# PCB.net
KiCad netlist of a schematic drawn in EAGLE
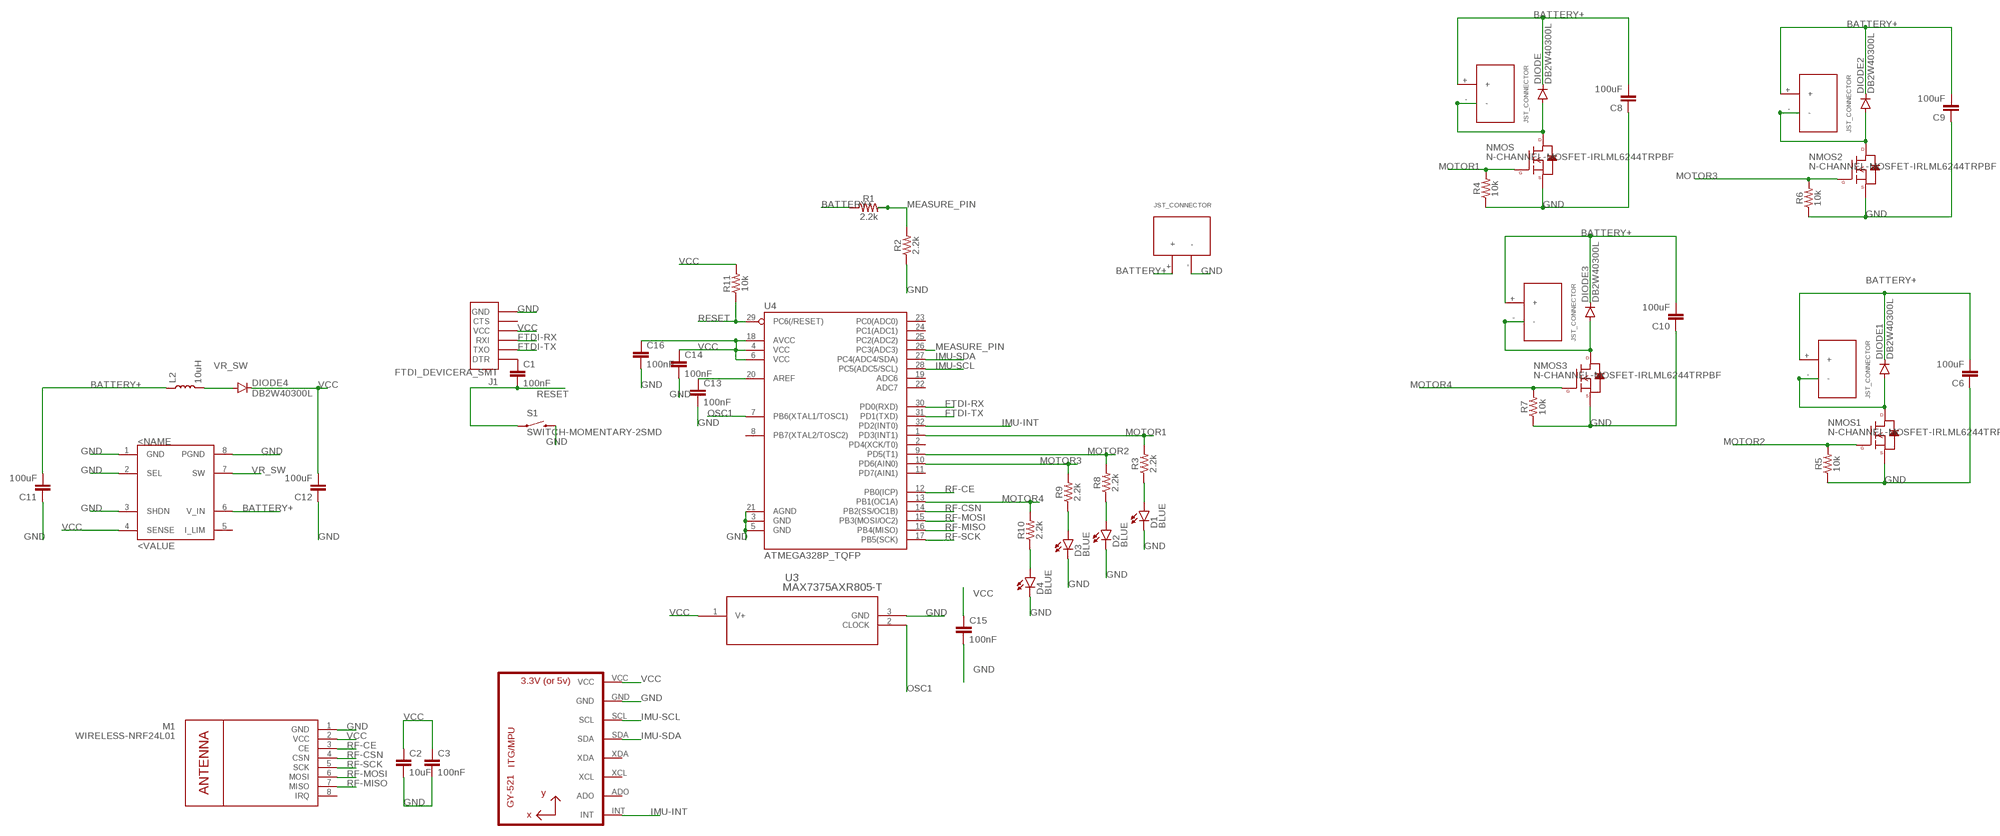
[diagram p0: schematic, sheet 1]

(export (version "E")
  (design (tool "Eeschema 10.0.6"))
  (components
    (comp (ref "BAT")
      (value "JST_CONNECTOR_FEMALE")
      (footprint "eagle-import:JST_CONNECTOR_FEMALE")
      (libsource (lib "eagle-import") (part "JST_CONNECTOR_FEMALE"))
    )
    (comp (ref "C1")
      (value "100nF")
      (footprint "eagle-import:0603-CAP")
      (libsource (lib "eagle-import") (part "0.1UF-25V(+80/-20%)(0603)"))
    )
    (comp (ref "C2")
      (value "10uF")
      (footprint "eagle-import:0603-CAP")
      (libsource (lib "eagle-import") (part "CAP0603-CAP"))
    )
    (comp (ref "C3")
      (value "100nF")
      (footprint "eagle-import:0603-CAP")
      (libsource (lib "eagle-import") (part "CAP0603-CAP"))
    )
    (comp (ref "C6")
      (value "100uF")
      (footprint "eagle-import:1206")
      (libsource (lib "eagle-import") (part "CAP1206"))
    )
    (comp (ref "C8")
      (value "100uF")
      (footprint "eagle-import:1206")
      (libsource (lib "eagle-import") (part "CAP1206"))
    )
    (comp (ref "C9")
      (value "100uF")
      (footprint "eagle-import:1206")
      (libsource (lib "eagle-import") (part "CAP1206"))
    )
    (comp (ref "C10")
      (value "100uF")
      (footprint "eagle-import:1206")
      (libsource (lib "eagle-import") (part "CAP1206"))
    )
    (comp (ref "C11")
      (value "100uF")
      (footprint "eagle-import:1206")
      (libsource (lib "eagle-import") (part "CAP1206"))
    )
    (comp (ref "C12")
      (value "100uF")
      (footprint "eagle-import:1206")
      (libsource (lib "eagle-import") (part "CAP1206"))
    )
    (comp (ref "C13")
      (value "100nF")
      (footprint "eagle-import:0603-CAP")
      (libsource (lib "eagle-import") (part "CAP0603-CAP"))
    )
    (comp (ref "C14")
      (value "100nF")
      (footprint "eagle-import:0603-CAP")
      (libsource (lib "eagle-import") (part "CAP0603-CAP"))
    )
    (comp (ref "C15")
      (value "100nF")
      (footprint "eagle-import:0603-CAP")
      (libsource (lib "eagle-import") (part "0.1UF-25V(+80/-20%)(0603)"))
    )
    (comp (ref "C16")
      (value "100nF")
      (footprint "eagle-import:0603-CAP")
      (libsource (lib "eagle-import") (part "CAP0603-CAP"))
    )
    (comp (ref "D1")
      (value "BLUE")
      (footprint "eagle-import:LED-0603")
      (fields (field (name "SPICEPREFIX") "D"))
      (libsource (lib "eagle-import") (part "LED-BLUE0603"))
    )
    (comp (ref "D2")
      (value "BLUE")
      (footprint "eagle-import:LED-0603")
      (libsource (lib "eagle-import") (part "LED-BLUE0603"))
    )
    (comp (ref "D3")
      (value "BLUE")
      (footprint "eagle-import:LED-0603")
      (libsource (lib "eagle-import") (part "LED-BLUE0603"))
    )
    (comp (ref "D4")
      (value "BLUE")
      (footprint "eagle-import:LED-0603")
      (libsource (lib "eagle-import") (part "LED-BLUE0603"))
    )
    (comp (ref "DIODE")
      (value "DB2W40300L")
      (footprint "eagle-import:MINI2-F3-B")
      (libsource (lib "eagle-import") (part "DB2W40300L"))
    )
    (comp (ref "DIODE1")
      (value "DB2W40300L")
      (footprint "eagle-import:MINI2-F3-B")
      (libsource (lib "eagle-import") (part "DB2W40300L"))
    )
    (comp (ref "DIODE2")
      (value "DB2W40300L")
      (footprint "eagle-import:MINI2-F3-B")
      (libsource (lib "eagle-import") (part "DB2W40300L"))
    )
    (comp (ref "DIODE3")
      (value "DB2W40300L")
      (footprint "eagle-import:MINI2-F3-B")
      (libsource (lib "eagle-import") (part "DB2W40300L"))
    )
    (comp (ref "DIODE4")
      (value "DB2W40300L")
      (footprint "eagle-import:MINI2-F3-B")
      (libsource (lib "eagle-import") (part "DB2W40300L"))
    )
    (comp (ref "J1")
      (value "FTDI_DEVICERA_SMT")
      (footprint "eagle-import:FTDI_DEVICE_RA_SMT")
      (libsource (lib "eagle-import") (part "FTDI_DEVICERA_SMT"))
    )
    (comp (ref "L2")
      (value "10uH")
      (footprint "eagle-import:0603")
      (libsource (lib "eagle-import") (part "INDUCTOR-0603-33NH"))
    )
    (comp (ref "M1")
      (value "WIRELESS-NRF24L01")
      (footprint "eagle-import:WIRELESS-NRF24L01")
      (libsource (lib "eagle-import") (part "WIRELESS-NRF24L01"))
    )
    (comp (ref "MOTOR")
      (value "JST_CONNECTOR_FEMALE")
      (footprint "eagle-import:JST_CONNECTOR_FEMALE")
      (libsource (lib "eagle-import") (part "JST_CONNECTOR_FEMALE"))
    )
    (comp (ref "MOTOR1")
      (value "JST_CONNECTOR_FEMALE")
      (footprint "eagle-import:JST_CONNECTOR_FEMALE")
      (libsource (lib "eagle-import") (part "JST_CONNECTOR_FEMALE"))
    )
    (comp (ref "MOTOR2")
      (value "JST_CONNECTOR_FEMALE")
      (footprint "eagle-import:JST_CONNECTOR_FEMALE")
      (libsource (lib "eagle-import") (part "JST_CONNECTOR_FEMALE"))
    )
    (comp (ref "MOTOR3")
      (value "JST_CONNECTOR_FEMALE")
      (footprint "eagle-import:JST_CONNECTOR_FEMALE")
      (libsource (lib "eagle-import") (part "JST_CONNECTOR_FEMALE"))
    )
    (comp (ref "NMOS")
      (value "N-CHANNEL-MOSFET-IRLML6244TRPBF")
      (footprint "eagle-import:SOT23-3")
      (libsource (lib "eagle-import") (part "N-CHANNEL-MOSFET-IRLML6244TRPBF"))
    )
    (comp (ref "NMOS1")
      (value "N-CHANNEL-MOSFET-IRLML6244TRPBF")
      (footprint "eagle-import:SOT23-3")
      (libsource (lib "eagle-import") (part "N-CHANNEL-MOSFET-IRLML6244TRPBF"))
    )
    (comp (ref "NMOS2")
      (value "N-CHANNEL-MOSFET-IRLML6244TRPBF")
      (footprint "eagle-import:SOT23-3")
      (libsource (lib "eagle-import") (part "N-CHANNEL-MOSFET-IRLML6244TRPBF"))
    )
    (comp (ref "NMOS3")
      (value "N-CHANNEL-MOSFET-IRLML6244TRPBF")
      (footprint "eagle-import:SOT23-3")
      (libsource (lib "eagle-import") (part "N-CHANNEL-MOSFET-IRLML6244TRPBF"))
    )
    (comp (ref "R1")
      (value "2.2k")
      (footprint "eagle-import:0603")
      (libsource (lib "eagle-import") (part "2.2KOHM-0603-1/10W-1%"))
    )
    (comp (ref "R2")
      (value "2.2k")
      (footprint "eagle-import:0603")
      (libsource (lib "eagle-import") (part "2.2KOHM-0603-1/10W-1%"))
    )
    (comp (ref "R3")
      (value "2.2k")
      (footprint "eagle-import:0603")
      (fields (field (name "SPICEPREFIX") "R"))
      (libsource (lib "eagle-import") (part "2.2KOHM-0603-1/10W-1%"))
    )
    (comp (ref "R4")
      (value "10k")
      (footprint "eagle-import:0603")
      (libsource (lib "eagle-import") (part "2.2KOHM-0603-1/10W-1%"))
    )
    (comp (ref "R5")
      (value "10k")
      (footprint "eagle-import:0603")
      (libsource (lib "eagle-import") (part "2.2KOHM-0603-1/10W-1%"))
    )
    (comp (ref "R6")
      (value "10k")
      (footprint "eagle-import:0603")
      (libsource (lib "eagle-import") (part "2.2KOHM-0603-1/10W-1%"))
    )
    (comp (ref "R7")
      (value "10k")
      (footprint "eagle-import:0603")
      (libsource (lib "eagle-import") (part "2.2KOHM-0603-1/10W-1%"))
    )
    (comp (ref "R8")
      (value "2.2k")
      (footprint "eagle-import:0603")
      (libsource (lib "eagle-import") (part "2.2KOHM-0603-1/10W-1%"))
    )
    (comp (ref "R9")
      (value "2.2k")
      (footprint "eagle-import:0603")
      (libsource (lib "eagle-import") (part "2.2KOHM-0603-1/10W-1%"))
    )
    (comp (ref "R10")
      (value "2.2k")
      (footprint "eagle-import:0603")
      (libsource (lib "eagle-import") (part "2.2KOHM-0603-1/10W-1%"))
    )
    (comp (ref "R11")
      (value "10k")
      (footprint "eagle-import:0603")
      (libsource (lib "eagle-import") (part "2.2KOHM-0603-1/10W-1%"))
    )
    (comp (ref "S1")
      (value "SWITCH-MOMENTARY-2SMD")
      (footprint "eagle-import:TACTILE-SWITCH-SMD")
      (libsource (lib "eagle-import") (part "SWITCH-MOMENTARY-2SMD"))
    )
    (comp (ref "U$4")
      (value "LT1300CS8#PBF-NDLT1300CS8#PBF-ND")
      (footprint "eagle-import:SOIC-8_S")
      (libsource (lib "eagle-import") (part "LT1300CS8#PBF-NDLT1300CS8#PBF-ND"))
    )
    (comp (ref "U2")
      (value "GY-521MPU6050")
      (footprint "eagle-import:GY-521")
      (libsource (lib "eagle-import") (part "GY-521MPU6050"))
    )
    (comp (ref "U3")
      (value "MAX7375AXR805-T")
      (footprint "eagle-import:21-0075D")
      (fields (field (name "MF") "Maxim Integrated") (field (name "MP") "MAX7375AXR805+T"))
      (libsource (lib "eagle-import") (part "MAX7375AXR805-T"))
    )
    (comp (ref "U4")
      (value "ATMEGA328P_TQFP")
      (footprint "eagle-import:TQFP32-08")
      (libsource (lib "eagle-import") (part "ATMEGA328P_TQFP"))
    )
  )
  (nets
    (net (code "1") (name "BATTERY+") (class "Default")
      (node (ref "BAT") (pin "+") (pinfunction "+_+") (pintype "bidirectional"))
      (node (ref "C10") (pin "2") (pinfunction "2_2") (pintype "passive"))
      (node (ref "C11") (pin "2") (pinfunction "2_2") (pintype "passive"))
      (node (ref "C6") (pin "2") (pinfunction "2_2") (pintype "passive"))
      (node (ref "C8") (pin "2") (pinfunction "2_2") (pintype "passive"))
      (node (ref "C9") (pin "2") (pinfunction "2_2") (pintype "passive"))
      (node (ref "DIODE") (pin "NEG") (pinfunction "GPIN_NEG") (pintype "passive"))
      (node (ref "DIODE1") (pin "NEG") (pinfunction "GPIN_NEG") (pintype "passive"))
      (node (ref "DIODE2") (pin "NEG") (pinfunction "GPIN_NEG") (pintype "passive"))
      (node (ref "DIODE3") (pin "NEG") (pinfunction "GPIN_NEG") (pintype "passive"))
      (node (ref "L2") (pin "1") (pinfunction "1_1") (pintype "passive"))
      (node (ref "MOTOR") (pin "+") (pinfunction "+_+") (pintype "bidirectional"))
      (node (ref "MOTOR1") (pin "+") (pinfunction "+_+") (pintype "bidirectional"))
      (node (ref "MOTOR2") (pin "+") (pinfunction "+_+") (pintype "bidirectional"))
      (node (ref "MOTOR3") (pin "+") (pinfunction "+_+") (pintype "bidirectional"))
      (node (ref "R1") (pin "1") (pinfunction "1_1") (pintype "passive"))
      (node (ref "U$4") (pin "6") (pinfunction "V_IN_6") (pintype "bidirectional"))
    )
    (net (code "2") (name "FTDI-RX") (class "Default")
      (node (ref "J1") (pin "3") (pinfunction "RXI_3") (pintype "bidirectional"))
      (node (ref "U4") (pin "30") (pinfunction "PD0(RXD)_30") (pintype "bidirectional"))
    )
    (net (code "3") (name "FTDI-TX") (class "Default")
      (node (ref "J1") (pin "2") (pinfunction "TXO_2") (pintype "bidirectional"))
      (node (ref "U4") (pin "31") (pinfunction "PD1(TXD)_31") (pintype "bidirectional"))
    )
    (net (code "4") (name "GND") (class "Default")
      (node (ref "BAT") (pin "-") (pinfunction "-_-") (pintype "bidirectional"))
      (node (ref "C10") (pin "1") (pinfunction "1_1") (pintype "passive"))
      (node (ref "C11") (pin "1") (pinfunction "1_1") (pintype "passive"))
      (node (ref "C12") (pin "1") (pinfunction "1_1") (pintype "passive"))
      (node (ref "C13") (pin "2") (pinfunction "2_2") (pintype "passive"))
      (node (ref "C14") (pin "2") (pinfunction "2_2") (pintype "passive"))
      (node (ref "C15") (pin "2") (pinfunction "2_2") (pintype "passive"))
      (node (ref "C16") (pin "2") (pinfunction "2_2") (pintype "passive"))
      (node (ref "C2") (pin "2") (pinfunction "2_2") (pintype "passive"))
      (node (ref "C3") (pin "2") (pinfunction "2_2") (pintype "passive"))
      (node (ref "C6") (pin "1") (pinfunction "1_1") (pintype "passive"))
      (node (ref "C8") (pin "1") (pinfunction "1_1") (pintype "passive"))
      (node (ref "C9") (pin "1") (pinfunction "1_1") (pintype "passive"))
      (node (ref "D1") (pin "C") (pinfunction "C_C") (pintype "passive"))
      (node (ref "D2") (pin "C") (pinfunction "C_C") (pintype "passive"))
      (node (ref "D3") (pin "C") (pinfunction "C_C") (pintype "passive"))
      (node (ref "D4") (pin "C") (pinfunction "C_C") (pintype "passive"))
      (node (ref "J1") (pin "6") (pinfunction "GND_6") (pintype "bidirectional"))
      (node (ref "M1") (pin "1") (pinfunction "GND_1") (pintype "power_in"))
      (node (ref "NMOS") (pin "2") (pinfunction "S_2") (pintype "passive"))
      (node (ref "NMOS1") (pin "2") (pinfunction "S_2") (pintype "passive"))
      (node (ref "NMOS2") (pin "2") (pinfunction "S_2") (pintype "passive"))
      (node (ref "NMOS3") (pin "2") (pinfunction "S_2") (pintype "passive"))
      (node (ref "R2") (pin "1") (pinfunction "1_1") (pintype "passive"))
      (node (ref "R4") (pin "1") (pinfunction "1_1") (pintype "passive"))
      (node (ref "R5") (pin "1") (pinfunction "1_1") (pintype "passive"))
      (node (ref "R6") (pin "1") (pinfunction "1_1") (pintype "passive"))
      (node (ref "R7") (pin "1") (pinfunction "1_1") (pintype "passive"))
      (node (ref "S1") (pin "3") (pinfunction "2_3") (pintype "passive"))
      (node (ref "U$4") (pin "1") (pinfunction "GND_1") (pintype "bidirectional"))
      (node (ref "U$4") (pin "2") (pinfunction "SEL_2") (pintype "bidirectional"))
      (node (ref "U$4") (pin "3") (pinfunction "SHDN_3") (pintype "bidirectional"))
      (node (ref "U$4") (pin "8") (pinfunction "PGND_8") (pintype "bidirectional"))
      (node (ref "U2") (pin "GND") (pinfunction "GND_GND") (pintype "bidirectional"))
      (node (ref "U3") (pin "3") (pinfunction "GND_3") (pintype "power_in"))
      (node (ref "U4") (pin "21") (pinfunction "AGND_21") (pintype "bidirectional"))
      (node (ref "U4") (pin "3") (pinfunction "GND_3") (pintype "bidirectional"))
      (node (ref "U4") (pin "5") (pinfunction "GND_5") (pintype "bidirectional"))
    )
    (net (code "5") (name "IMU-INT") (class "Default")
      (node (ref "U2") (pin "INT") (pinfunction "INT_INT") (pintype "bidirectional"))
      (node (ref "U4") (pin "32") (pinfunction "PD2(INT0)_32") (pintype "bidirectional"))
    )
    (net (code "6") (name "IMU-SCL") (class "Default")
      (node (ref "U2") (pin "SCL") (pinfunction "SCL_SCL") (pintype "bidirectional"))
      (node (ref "U4") (pin "28") (pinfunction "PC5(ADC5/SCL)_28") (pintype "bidirectional"))
    )
    (net (code "7") (name "IMU-SDA") (class "Default")
      (node (ref "U2") (pin "SDA") (pinfunction "SDA_SDA") (pintype "bidirectional"))
      (node (ref "U4") (pin "27") (pinfunction "PC4(ADC4/SDA)_27") (pintype "bidirectional"))
    )
    (net (code "8") (name "MEASURE_PIN") (class "Default")
      (node (ref "R1") (pin "2") (pinfunction "2_2") (pintype "passive"))
      (node (ref "R2") (pin "2") (pinfunction "2_2") (pintype "passive"))
      (node (ref "U4") (pin "26") (pinfunction "PC3(ADC3)_26") (pintype "bidirectional"))
    )
    (net (code "9") (name "MOTOR1") (class "Default")
      (node (ref "NMOS") (pin "1") (pinfunction "G_1") (pintype "passive"))
      (node (ref "R3") (pin "2") (pinfunction "2_2") (pintype "passive"))
      (node (ref "R4") (pin "2") (pinfunction "2_2") (pintype "passive"))
      (node (ref "U4") (pin "1") (pinfunction "PD3(INT1)_1") (pintype "bidirectional"))
    )
    (net (code "10") (name "MOTOR2") (class "Default")
      (node (ref "NMOS1") (pin "1") (pinfunction "G_1") (pintype "passive"))
      (node (ref "R5") (pin "2") (pinfunction "2_2") (pintype "passive"))
      (node (ref "R8") (pin "2") (pinfunction "2_2") (pintype "passive"))
      (node (ref "U4") (pin "9") (pinfunction "PD5(T1)_9") (pintype "bidirectional"))
    )
    (net (code "11") (name "MOTOR3") (class "Default")
      (node (ref "NMOS2") (pin "1") (pinfunction "G_1") (pintype "passive"))
      (node (ref "R6") (pin "2") (pinfunction "2_2") (pintype "passive"))
      (node (ref "R9") (pin "2") (pinfunction "2_2") (pintype "passive"))
      (node (ref "U4") (pin "10") (pinfunction "PD6(AIN0)_10") (pintype "bidirectional"))
    )
    (net (code "12") (name "MOTOR4") (class "Default")
      (node (ref "NMOS3") (pin "1") (pinfunction "G_1") (pintype "passive"))
      (node (ref "R10") (pin "2") (pinfunction "2_2") (pintype "passive"))
      (node (ref "R7") (pin "2") (pinfunction "2_2") (pintype "passive"))
      (node (ref "U4") (pin "13") (pinfunction "PB1(OC1A)_13") (pintype "bidirectional"))
    )
    (net (code "13") (name "Net-(D1-PadA)") (class "Default")
      (node (ref "D1") (pin "A") (pinfunction "A_A") (pintype "passive"))
      (node (ref "R3") (pin "1") (pinfunction "1_1") (pintype "passive"))
    )
    (net (code "14") (name "Net-(D2-PadA)") (class "Default")
      (node (ref "D2") (pin "A") (pinfunction "A_A") (pintype "passive"))
      (node (ref "R8") (pin "1") (pinfunction "1_1") (pintype "passive"))
    )
    (net (code "15") (name "Net-(D3-PadA)") (class "Default")
      (node (ref "D3") (pin "A") (pinfunction "A_A") (pintype "passive"))
      (node (ref "R9") (pin "1") (pinfunction "1_1") (pintype "passive"))
    )
    (net (code "16") (name "Net-(D4-PadA)") (class "Default")
      (node (ref "D4") (pin "A") (pinfunction "A_A") (pintype "passive"))
      (node (ref "R10") (pin "1") (pinfunction "1_1") (pintype "passive"))
    )
    (net (code "17") (name "Net-(DIODE-PPIN)") (class "Default")
      (node (ref "DIODE") (pin "POS") (pinfunction "PPIN_POS") (pintype "passive"))
      (node (ref "MOTOR") (pin "-") (pinfunction "-_-") (pintype "bidirectional"))
      (node (ref "NMOS") (pin "3") (pinfunction "D_3") (pintype "passive"))
    )
    (net (code "18") (name "Net-(DIODE1-PPIN)") (class "Default")
      (node (ref "DIODE1") (pin "POS") (pinfunction "PPIN_POS") (pintype "passive"))
      (node (ref "MOTOR1") (pin "-") (pinfunction "-_-") (pintype "bidirectional"))
      (node (ref "NMOS1") (pin "3") (pinfunction "D_3") (pintype "passive"))
    )
    (net (code "19") (name "Net-(DIODE2-PPIN)") (class "Default")
      (node (ref "DIODE2") (pin "POS") (pinfunction "PPIN_POS") (pintype "passive"))
      (node (ref "MOTOR2") (pin "-") (pinfunction "-_-") (pintype "bidirectional"))
      (node (ref "NMOS2") (pin "3") (pinfunction "D_3") (pintype "passive"))
    )
    (net (code "20") (name "Net-(DIODE3-PPIN)") (class "Default")
      (node (ref "DIODE3") (pin "POS") (pinfunction "PPIN_POS") (pintype "passive"))
      (node (ref "MOTOR3") (pin "-") (pinfunction "-_-") (pintype "bidirectional"))
      (node (ref "NMOS3") (pin "3") (pinfunction "D_3") (pintype "passive"))
    )
    (net (code "21") (name "Net-(J1-DTR)") (class "Default")
      (node (ref "C1") (pin "1") (pinfunction "1_1") (pintype "passive"))
      (node (ref "J1") (pin "1") (pinfunction "DTR_1") (pintype "bidirectional"))
    )
    (net (code "22") (name "Net-(U4-AREF)") (class "Default")
      (node (ref "C13") (pin "1") (pinfunction "1_1") (pintype "passive"))
      (node (ref "U4") (pin "20") (pinfunction "AREF_20") (pintype "bidirectional"))
    )
    (net (code "23") (name "OSC1") (class "Default")
      (node (ref "U3") (pin "2") (pinfunction "CLOCK_2") (pintype "output"))
      (node (ref "U4") (pin "7") (pinfunction "PB6(XTAL1/TOSC1)_7") (pintype "bidirectional"))
    )
    (net (code "24") (name "RESET") (class "Default")
      (node (ref "C1") (pin "2") (pinfunction "2_2") (pintype "passive"))
      (node (ref "R11") (pin "1") (pinfunction "1_1") (pintype "passive"))
      (node (ref "S1") (pin "1") (pinfunction "1_1") (pintype "passive"))
      (node (ref "U4") (pin "29") (pinfunction "PC6(/RESET)_29") (pintype "bidirectional"))
    )
    (net (code "25") (name "RF-CE") (class "Default")
      (node (ref "M1") (pin "3") (pinfunction "CE_3") (pintype "bidirectional"))
      (node (ref "U4") (pin "12") (pinfunction "PB0(ICP)_12") (pintype "bidirectional"))
    )
    (net (code "26") (name "RF-CSN") (class "Default")
      (node (ref "M1") (pin "4") (pinfunction "CSN_4") (pintype "bidirectional"))
      (node (ref "U4") (pin "14") (pinfunction "PB2(SS/OC1B)_14") (pintype "bidirectional"))
    )
    (net (code "27") (name "RF-MISO") (class "Default")
      (node (ref "M1") (pin "7") (pinfunction "MISO_7") (pintype "bidirectional"))
      (node (ref "U4") (pin "16") (pinfunction "PB4(MISO)_16") (pintype "bidirectional"))
    )
    (net (code "28") (name "RF-MOSI") (class "Default")
      (node (ref "M1") (pin "6") (pinfunction "MOSI_6") (pintype "bidirectional"))
      (node (ref "U4") (pin "15") (pinfunction "PB3(MOSI/OC2)_15") (pintype "bidirectional"))
    )
    (net (code "29") (name "RF-SCK") (class "Default")
      (node (ref "M1") (pin "5") (pinfunction "SCK_5") (pintype "bidirectional"))
      (node (ref "U4") (pin "17") (pinfunction "PB5(SCK)_17") (pintype "bidirectional"))
    )
    (net (code "30") (name "VCC") (class "Default")
      (node (ref "C12") (pin "2") (pinfunction "2_2") (pintype "passive"))
      (node (ref "C14") (pin "1") (pinfunction "1_1") (pintype "passive"))
      (node (ref "C15") (pin "1") (pinfunction "1_1") (pintype "passive"))
      (node (ref "C16") (pin "1") (pinfunction "1_1") (pintype "passive"))
      (node (ref "C2") (pin "1") (pinfunction "1_1") (pintype "passive"))
      (node (ref "C3") (pin "1") (pinfunction "1_1") (pintype "passive"))
      (node (ref "DIODE4") (pin "NEG") (pinfunction "GPIN_NEG") (pintype "passive"))
      (node (ref "J1") (pin "4") (pinfunction "VCC_4") (pintype "bidirectional"))
      (node (ref "M1") (pin "2") (pinfunction "VCC_2") (pintype "power_in"))
      (node (ref "R11") (pin "2") (pinfunction "2_2") (pintype "passive"))
      (node (ref "U$4") (pin "4") (pinfunction "SENSE_4") (pintype "bidirectional"))
      (node (ref "U2") (pin "VCC") (pinfunction "VCC_VCC") (pintype "bidirectional"))
      (node (ref "U3") (pin "1") (pinfunction "V+_1") (pintype "power_in"))
      (node (ref "U4") (pin "18") (pinfunction "AVCC_18") (pintype "bidirectional"))
      (node (ref "U4") (pin "4") (pinfunction "VCC_4") (pintype "bidirectional"))
      (node (ref "U4") (pin "6") (pinfunction "VCC_6") (pintype "bidirectional"))
    )
    (net (code "31") (name "VR_SW") (class "Default")
      (node (ref "DIODE4") (pin "POS") (pinfunction "PPIN_POS") (pintype "passive"))
      (node (ref "L2") (pin "2") (pinfunction "2_2") (pintype "passive"))
      (node (ref "U$4") (pin "7") (pinfunction "SW_7") (pintype "bidirectional"))
    )
    (net (code "32") (name "unconnected-(J1-CTS-Pad5)") (class "Default")
      (node (ref "J1") (pin "5") (pinfunction "CTS_5") (pintype "bidirectional"))
    )
    (net (code "33") (name "unconnected-(M1-IRQ-Pad8)") (class "Default")
      (node (ref "M1") (pin "8") (pinfunction "IRQ_8") (pintype "bidirectional"))
    )
    (net (code "34") (name "unconnected-(U$4-I_LIM-Pad5)") (class "Default")
      (node (ref "U$4") (pin "5") (pinfunction "I_LIM_5") (pintype "bidirectional"))
    )
    (net (code "35") (name "unconnected-(U2-PadADO)") (class "Default")
      (node (ref "U2") (pin "ADO") (pinfunction "ADO_ADO") (pintype "bidirectional"))
    )
    (net (code "36") (name "unconnected-(U2-PadXCL)") (class "Default")
      (node (ref "U2") (pin "XCL") (pinfunction "XCL_XCL") (pintype "bidirectional"))
    )
    (net (code "37") (name "unconnected-(U2-PadXDA)") (class "Default")
      (node (ref "U2") (pin "XDA") (pinfunction "XDA_XDA") (pintype "bidirectional"))
    )
    (net (code "38") (name "unconnected-(U4-ADC6-Pad19)") (class "Default")
      (node (ref "U4") (pin "19") (pinfunction "ADC6_19") (pintype "bidirectional"))
    )
    (net (code "39") (name "unconnected-(U4-ADC7-Pad22)") (class "Default")
      (node (ref "U4") (pin "22") (pinfunction "ADC7_22") (pintype "bidirectional"))
    )
    (net (code "40") (name "unconnected-(U4-PB7(XTAL2{slash}TOSC2)-Pad8)") (class "Default")
      (node (ref "U4") (pin "8") (pinfunction "PB7(XTAL2/TOSC2)_8") (pintype "bidirectional"))
    )
    (net (code "41") (name "unconnected-(U4-PC0(ADC0)-Pad23)") (class "Default")
      (node (ref "U4") (pin "23") (pinfunction "PC0(ADC0)_23") (pintype "bidirectional"))
    )
    (net (code "42") (name "unconnected-(U4-PC1(ADC1)-Pad24)") (class "Default")
      (node (ref "U4") (pin "24") (pinfunction "PC1(ADC1)_24") (pintype "bidirectional"))
    )
    (net (code "43") (name "unconnected-(U4-PC2(ADC2)-Pad25)") (class "Default")
      (node (ref "U4") (pin "25") (pinfunction "PC2(ADC2)_25") (pintype "bidirectional"))
    )
    (net (code "44") (name "unconnected-(U4-PD4(XCK{slash}T0)-Pad2)") (class "Default")
      (node (ref "U4") (pin "2") (pinfunction "PD4(XCK/T0)_2") (pintype "bidirectional"))
    )
    (net (code "45") (name "unconnected-(U4-PD7(AIN1)-Pad11)") (class "Default")
      (node (ref "U4") (pin "11") (pinfunction "PD7(AIN1)_11") (pintype "bidirectional"))
    )
  )
)
